# SensorSquare.net
KiCad netlist of a schematic drawn in Altium Designer
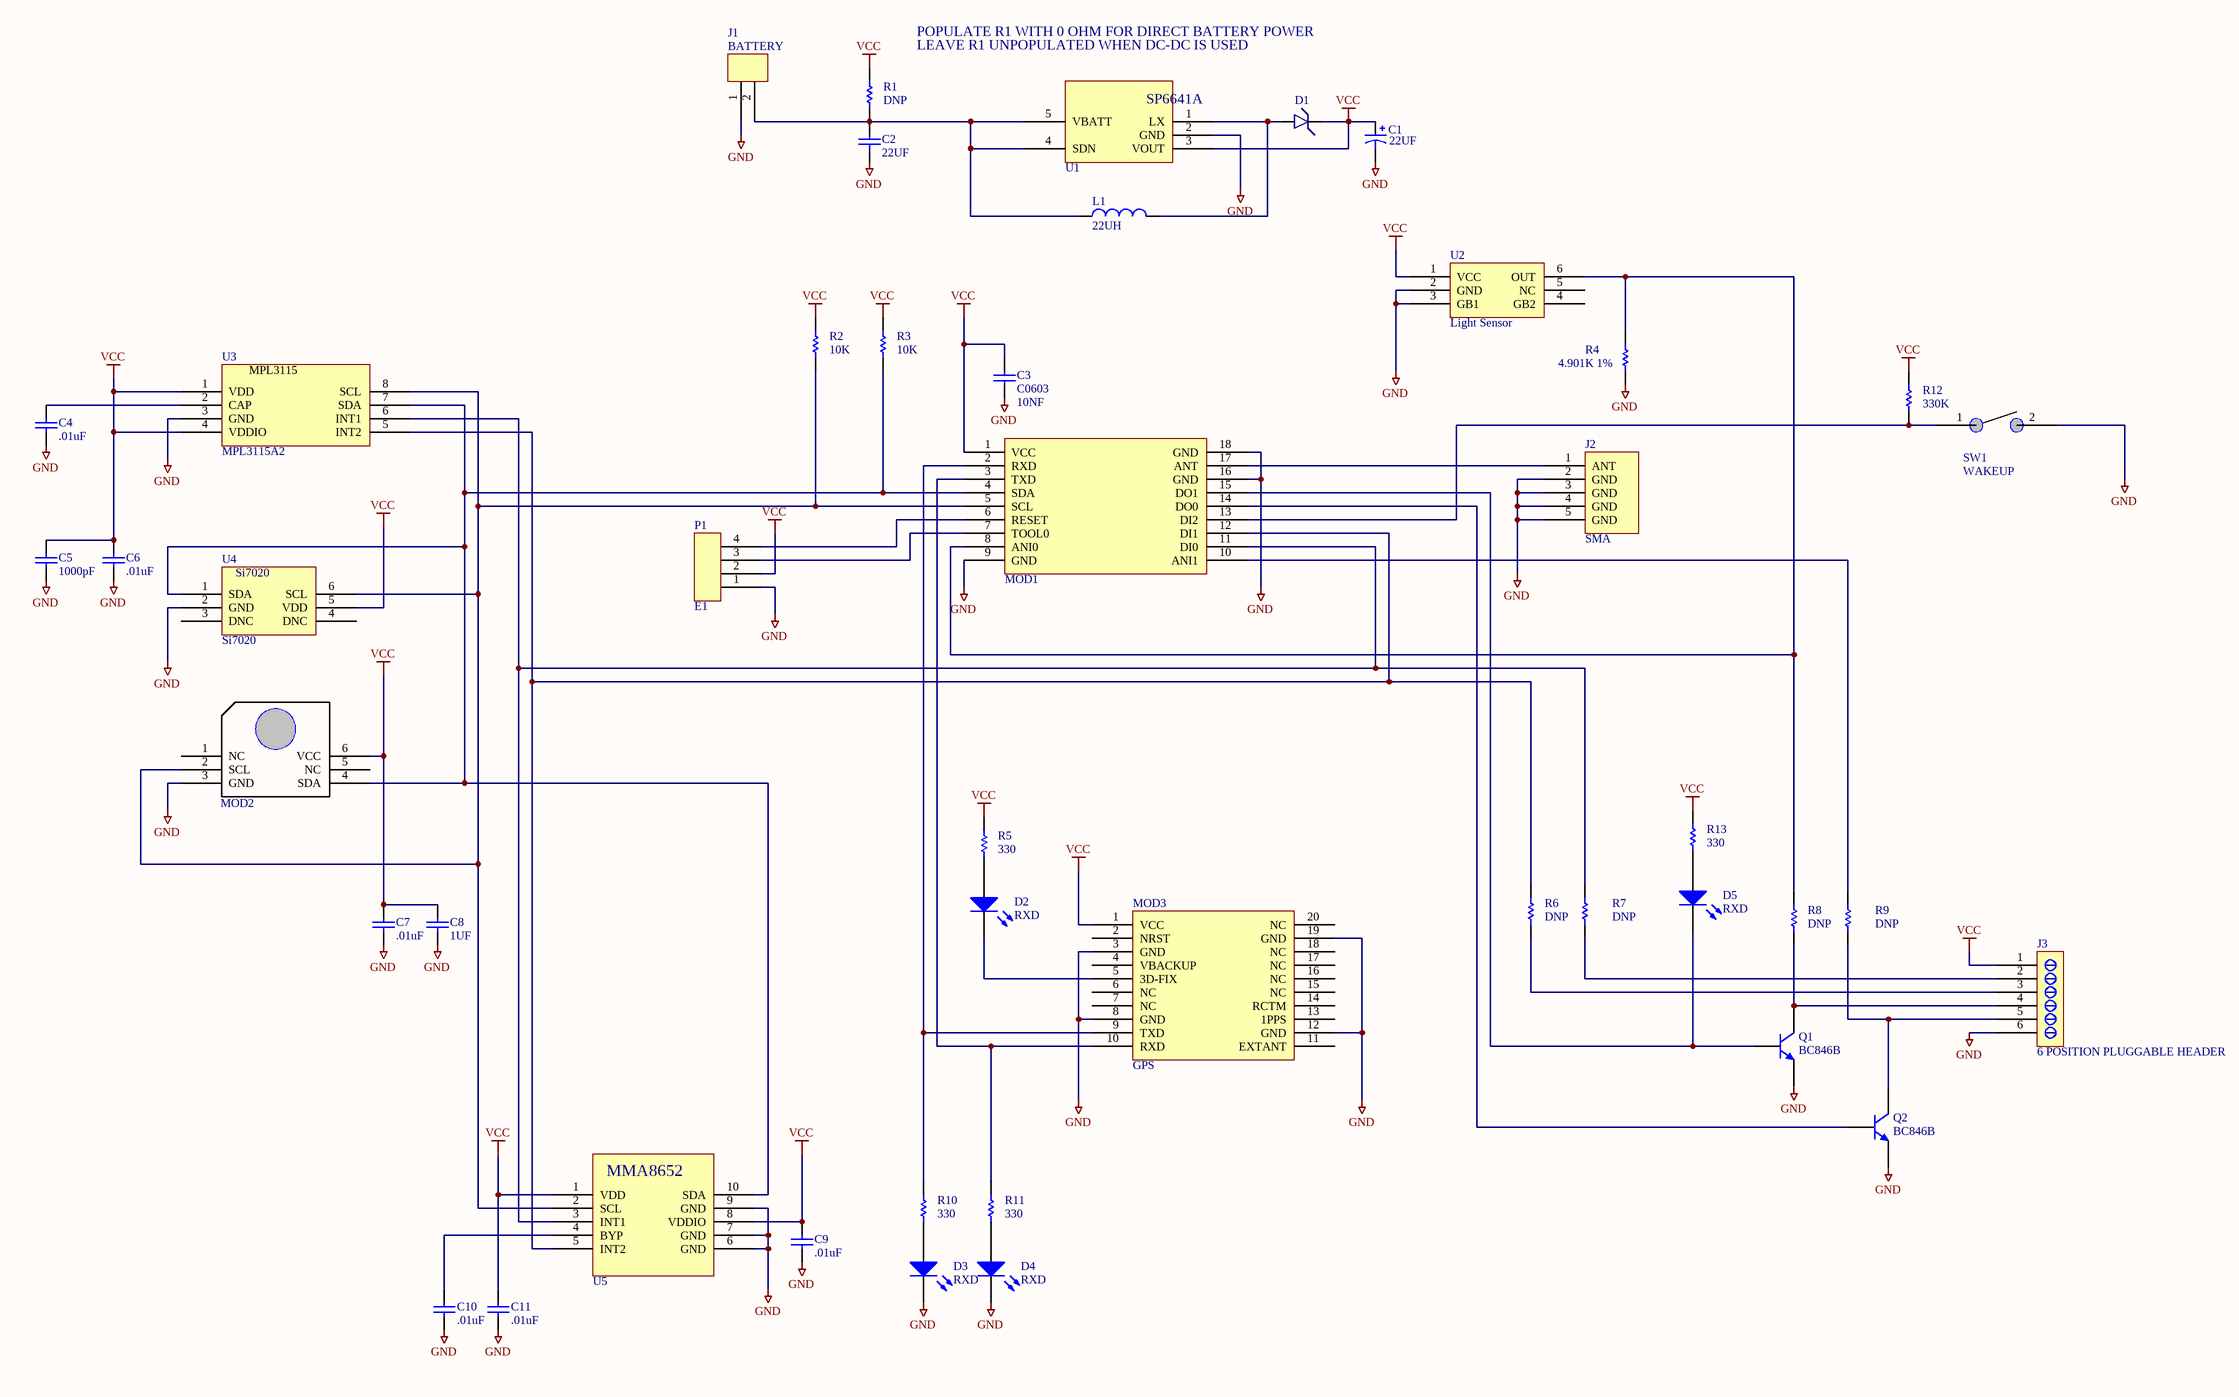
[diagram p0: SensorSquare.SchDoc]

(export (version "E")
  (design (tool "Eeschema 10.0.6"))
  (components
    (comp (ref "C1")
      (value "22UF")
      (footprint "1812")
      (description "Polarized Capacitor (Surface Mount)")
      (fields (field (name "VENDOR PART NUMBER") "647-F930J336MBA") (field (name "MANUFACTURER") "AVX"))
      (libsource (lib "Miscellaneous Devices") (part "Cap Pol3"))
    )
    (comp (ref "C2")
      (value "22UF")
      (footprint "1210")
      (description "Ceramic Chip Capacitor - Standard")
      (fields
        (field (name "MANUFACTURER") "AVX")
        (field (name "MANUFACTURER PART NUMBER") "TPSB107K006R0400")
      )
      (libsource (lib "KEMET Chip Capacitor") (part "C1210"))
    )
    (comp (ref "C3")
      (value "C0603")
      (footprint "0603")
      (description "Ceramic Chip Capacitor - Standard")
      (fields
        (field (name "ALTIUM_VALUE") "10NF")
        (field (name "VENDOR PART NUMBER") "140-CC504B103K-RC")
        (field (name "MANUFACTURER") "XICON")
      )
      (libsource (lib "KEMET Chip Capacitor") (part "C0603"))
    )
    (comp (ref "C4")
      (value ".01uF")
      (footprint "D6_0603_RES")
      (description "Ceramic Chip Capacitor - Standard")
      (fields
        (field (name "MANUFACTURER") "VISHAY")
        (field (name "MANUFACTURER PART NUMBER") "VJ0603A150JXACW1BC")
      )
      (libsource (lib "KEMET Chip Capacitor") (part "C1210"))
    )
    (comp (ref "C5")
      (value "1000pF")
      (footprint "D6_0603_RES")
      (description "Ceramic Chip Capacitor - Standard")
      (fields
        (field (name "MANUFACTURER") "VISHAY")
        (field (name "MANUFACTURER PART NUMBER") "VJ0603A150JXACW1BC")
      )
      (libsource (lib "KEMET Chip Capacitor") (part "C1210"))
    )
    (comp (ref "C6")
      (value ".01uF")
      (footprint "D6_0603_RES")
      (description "Ceramic Chip Capacitor - Standard")
      (fields
        (field (name "MANUFACTURER") "VISHAY")
        (field (name "MANUFACTURER PART NUMBER") "VJ0603A150JXACW1BC")
      )
      (libsource (lib "KEMET Chip Capacitor") (part "C1210"))
    )
    (comp (ref "C7")
      (value ".01uF")
      (footprint "D6_0603_RES")
      (description "Ceramic Chip Capacitor - Standard")
      (fields
        (field (name "MANUFACTURER") "VISHAY")
        (field (name "MANUFACTURER PART NUMBER") "VJ0603A150JXACW1BC")
      )
      (libsource (lib "KEMET Chip Capacitor") (part "C1210"))
    )
    (comp (ref "C8")
      (value "1UF")
      (footprint "D6_0603_RES")
      (description "Ceramic Chip Capacitor - Standard")
      (fields
        (field (name "MANUFACTURER") "VISHAY")
        (field (name "MANUFACTURER PART NUMBER") "VJ0603A150JXACW1BC")
      )
      (libsource (lib "KEMET Chip Capacitor") (part "C1210"))
    )
    (comp (ref "C9")
      (value ".01uF")
      (footprint "D6_0603_RES")
      (description "Ceramic Chip Capacitor - Standard")
      (fields
        (field (name "MANUFACTURER") "VISHAY")
        (field (name "MANUFACTURER PART NUMBER") "VJ0603A150JXACW1BC")
      )
      (libsource (lib "KEMET Chip Capacitor") (part "C1210"))
    )
    (comp (ref "C10")
      (value ".01uF")
      (footprint "D6_0603_RES")
      (description "Ceramic Chip Capacitor - Standard")
      (fields
        (field (name "MANUFACTURER") "VISHAY")
        (field (name "MANUFACTURER PART NUMBER") "VJ0603A150JXACW1BC")
      )
      (libsource (lib "KEMET Chip Capacitor") (part "C1210"))
    )
    (comp (ref "C11")
      (value ".01uF")
      (footprint "D6_0603_RES")
      (description "Ceramic Chip Capacitor - Standard")
      (fields
        (field (name "MANUFACTURER") "VISHAY")
        (field (name "MANUFACTURER PART NUMBER") "VJ0603A150JXACW1BC")
      )
      (libsource (lib "KEMET Chip Capacitor") (part "C1210"))
    )
    (comp (ref "D1")
      (value "SCHOTKY DIODE")
      (footprint "SOD123")
      (description "SCHOTKY DIODE SOD-123")
      (fields (field (name "MANUFACTURER") "ST") (field (name "MANUFACTURER PART NUMBER") "STPS0520Z"))
      (libsource (lib "D6 Labs") (part "SCHOTKY DIODE"))
    )
    (comp (ref "D2")
      (value "RXD")
      (footprint "3.2X1.6X1.1")
      (description "Typical RED, GREEN, YELLOW, AMBER GaAs LED")
      (fields (field (name "PUBLISHER") "Altium Limited"))
      (libsource (lib "Miscellaneous Devices") (part "LED2"))
    )
    (comp (ref "D3")
      (value "RXD")
      (footprint "3.2X1.6X1.1")
      (description "Typical RED, GREEN, YELLOW, AMBER GaAs LED")
      (fields (field (name "PUBLISHER") "Altium Limited"))
      (libsource (lib "Miscellaneous Devices") (part "LED2"))
    )
    (comp (ref "D4")
      (value "RXD")
      (footprint "3.2X1.6X1.1")
      (description "Typical RED, GREEN, YELLOW, AMBER GaAs LED")
      (fields (field (name "PUBLISHER") "Altium Limited"))
      (libsource (lib "Miscellaneous Devices") (part "LED2"))
    )
    (comp (ref "D5")
      (value "RXD")
      (footprint "3.2X1.6X1.1")
      (description "Typical RED, GREEN, YELLOW, AMBER GaAs LED")
      (fields (field (name "PUBLISHER") "Altium Limited"))
      (libsource (lib "Miscellaneous Devices") (part "LED2"))
    )
    (comp (ref "J1")
      (value "BATTERY")
      (footprint "S2B-PH-SM4")
      (description "2 POSITION, 2MM RIGHT ANGLE CONNECTOR")
      (fields (field (name "MANUFACTURER") "JST") (field (name "MANUFACTURER PART NUMBER") "S2B-PH-SM4-TB"))
      (libsource (lib "D6 Connectors") (part "S2B-PH-SM4-TB"))
    )
    (comp (ref "J2")
      (value "SMA")
      (footprint "RPSMA-EDGEMOUNT")
      (libsource (lib "D6 Connectors") (part "SMA"))
    )
    (comp (ref "J3")
      (value "6 POSITION PLUGGABLE HEADER")
      (footprint "6POS 5.08MM PLUGGABLE")
      (fields
        (field (name "MANUFACTURER") "FCI CONN")
        (field (name "MANUFACTURER PART NUMBER") "20020110-H061A01LF")
        (field (name "VENDOR PART NUMBER") "649-20020110-H061A01LF")
      )
      (libsource (lib "D6 Connectors") (part "6 POSITION PLUGGABLE HEADER"))
    )
    (comp (ref "L1")
      (value "22UH")
      (footprint "INDC4532")
      (description "Inductor")
      (fields
        (field (name "MANUFACTURER") "TDK")
        (field (name "MANUFACTURER PART NUMBER") "NLC453232T-220K-PF")
      )
      (libsource (lib "Miscellaneous Devices") (part "Inductor"))
    )
    (comp (ref "MOD1")
      (value "WhiskerModule")
      (footprint "WHISKER_SMD_DOLLY")
      (description "Whisker Footprint")
      (libsource (lib "D6 Labs") (part "WhiskerModule"))
    )
    (comp (ref "MOD2")
      (value "IAQ_ENGINE")
      (footprint "IAQENGINE")
      (description "Indoor Air Quality Sensor Module")
      (libsource (lib "AppliedSensor") (part "IAQ_ENGINE"))
    )
    (comp (ref "MOD3")
      (value "GPS")
      (footprint "GPS-SOP20")
      (fields
        (field (name "MANUFACTURER") "GTOP")
        (field (name "MANUFACTURER PART NUMBER") "FGPMMOPA6H")
        (field (name "VENDOR PART NUMBER") "PID790")
      )
      (libsource (lib "adafruit") (part "ULTIMATEGPS"))
    )
    (comp (ref "P1")
      (value "E1")
      (footprint "2MM4PINHDR")
      (libsource (lib "D6 Connectors") (part "2MM4PINHDR"))
    )
    (comp (ref "Q1")
      (value "BC846B")
      (footprint "SOT23")
      (description "SOT23 NPN Silicon Planar General Purpose Transistor")
      (fields
        (field (name "MANUFACTURER") "ON SEMI")
        (field (name "MANUFACTURER PART NUMBER") "MMUN2232LT1G")
        (field (name "PUBLISHER") "Altium Limited")
      )
      (libsource (lib "Zetex Discrete BJT") (part "BC846B"))
    )
    (comp (ref "Q2")
      (value "BC846B")
      (footprint "SOT23")
      (description "SOT23 NPN Silicon Planar General Purpose Transistor")
      (fields
        (field (name "MANUFACTURER") "ON SEMI")
        (field (name "MANUFACTURER PART NUMBER") "MMUN2232LT1G")
        (field (name "PUBLISHER") "Altium Limited")
      )
      (libsource (lib "Zetex Discrete BJT") (part "BC846B"))
    )
    (comp (ref "R1")
      (value "DNP")
      (footprint "ERA-0603")
      (fields (field (name "VENDOR PART NUMBER") "301-330-RC") (field (name "MANUFACTURER") "XICON"))
      (libsource (lib "Panasonic Resistor") (part "ERA3Y"))
    )
    (comp (ref "R2")
      (value "10K")
      (footprint "3-0603")
      (fields (field (name "PUBLISHER") "Altium Limited"))
      (libsource (lib "Panasonic Resistor") (part "ERJ3BQ"))
    )
    (comp (ref "R3")
      (value "10K")
      (footprint "3-0603")
      (fields (field (name "PUBLISHER") "Altium Limited"))
      (libsource (lib "Panasonic Resistor") (part "ERJ3BQ"))
    )
    (comp (ref "R4")
      (value "4.901K 1%")
      (footprint "D6_0603_RES")
      (fields (field (name "VENDOR PART NUMBER") "301-100K-RC") (field (name "MANUFACTURER") "XICON"))
      (libsource (lib "Panasonic Resistor") (part "ERA3Y"))
    )
    (comp (ref "R5")
      (value "330")
      (footprint "ERA-0603")
      (fields (field (name "VENDOR PART NUMBER") "301-330-RC") (field (name "MANUFACTURER") "XICON"))
      (libsource (lib "Panasonic Resistor") (part "ERA3Y"))
    )
    (comp (ref "R6")
      (value "DNP")
      (footprint "ERA-0603")
      (fields (field (name "VENDOR PART NUMBER") "301-330-RC") (field (name "MANUFACTURER") "XICON"))
      (libsource (lib "Panasonic Resistor") (part "ERA3Y"))
    )
    (comp (ref "R7")
      (value "DNP")
      (footprint "ERA-0603")
      (fields (field (name "VENDOR PART NUMBER") "301-330-RC") (field (name "MANUFACTURER") "XICON"))
      (libsource (lib "Panasonic Resistor") (part "ERA3Y"))
    )
    (comp (ref "R8")
      (value "DNP")
      (footprint "ERA-0603")
      (fields (field (name "VENDOR PART NUMBER") "301-330-RC") (field (name "MANUFACTURER") "XICON"))
      (libsource (lib "Panasonic Resistor") (part "ERA3Y"))
    )
    (comp (ref "R9")
      (value "DNP")
      (footprint "ERA-0603")
      (fields (field (name "VENDOR PART NUMBER") "301-330-RC") (field (name "MANUFACTURER") "XICON"))
      (libsource (lib "Panasonic Resistor") (part "ERA3Y"))
    )
    (comp (ref "R10")
      (value "330")
      (footprint "ERA-0603")
      (fields (field (name "VENDOR PART NUMBER") "301-330-RC") (field (name "MANUFACTURER") "XICON"))
      (libsource (lib "Panasonic Resistor") (part "ERA3Y"))
    )
    (comp (ref "R11")
      (value "330")
      (footprint "ERA-0603")
      (fields (field (name "VENDOR PART NUMBER") "301-330-RC") (field (name "MANUFACTURER") "XICON"))
      (libsource (lib "Panasonic Resistor") (part "ERA3Y"))
    )
    (comp (ref "R12")
      (value "330K")
      (footprint "D6_0603_RES")
      (fields (field (name "VENDOR PART NUMBER") "301-100K-RC") (field (name "MANUFACTURER") "XICON"))
      (libsource (lib "Panasonic Resistor") (part "ERA3Y"))
    )
    (comp (ref "R13")
      (value "330")
      (footprint "ERA-0603")
      (fields (field (name "VENDOR PART NUMBER") "301-330-RC") (field (name "MANUFACTURER") "XICON"))
      (libsource (lib "Panasonic Resistor") (part "ERA3Y"))
    )
    (comp (ref "SW1")
      (value "WAKEUP")
      (footprint "MK23-35-B-2")
      (description "SMT Reed Switch")
      (fields (field (name "MANUFACTURER") "MEDER") (field (name "MANUFACTURER PART NUMBER") "MK23-35-B-2"))
      (libsource (lib "Meder") (part "MK23-35-B-2"))
    )
    (comp (ref "U1")
      (value "500MA ALKALINE D~{C}DC BOOST REGULATOR SOT-23")
      (footprint "SOT95P280X110-5N")
      (description "SP6641A")
      (fields
        (field (name "MANUFACTURER") "SIPEX")
        (field (name "MANUFACTURER PART NUMBER") "SP6641BEK-L-3-3")
      )
      (libsource (lib "exar") (part "500MA ALKALINE DC{backslash}DC BOOST REGULATOR SOT-23"))
    )
    (comp (ref "U2")
      (value "Light Sensor")
      (footprint "CUDFN6")
      (description "Ambient Light Sensor with Dark Comp")
      (fields
        (field (name "MANUFACTURER") "ON SEMI")
        (field (name "MANUFACTURER PART NUMBER") "NOA1212CUTAG")
      )
      (libsource (lib "On Semi") (part "NOA1212"))
    )
    (comp (ref "U3")
      (value "MPL3115A2")
      (footprint "LGA8")
      (description "Precision altimeter")
      (fields (field (name "MANUFACTURER") "FREESCALE") (field (name "VENDOR PART NUMBER") "841-MPL3115A2R1"))
      (libsource (lib "FreeScaleSensors") (part "MPL3115A2"))
    )
    (comp (ref "U4")
      (value "Si7020")
      (footprint "DFN6")
      (description "I2C Temperature and Humidity Sensor")
      (fields
        (field (name "VENDOR PART NUMBER") "634- Si7020-A10-GM")
        (field (name "MANUFACTURER") "SILICON LABORATORIES")
      )
      (libsource (lib "SiLabs") (part "Si7020"))
    )
    (comp (ref "U5")
      (value "MMA8652")
      (footprint "DFN10")
      (description "3-axis, 12-bit accelerometer")
      (fields
        (field (name "MANUFACTURER") "FREESCALE")
        (field (name "MANUFACTURER PART NUMBER") "863-NOA1212CUTAG")
      )
      (libsource (lib "FreeScaleSensors") (part "MMA8652"))
    )
  )
  (nets
    (net (code "1") (name "GND") (class "Default")
      (node (ref "C1") (pin "2") (pinfunction "2_2") (pintype "passive"))
      (node (ref "C10") (pin "1") (pinfunction "1_1") (pintype "passive"))
      (node (ref "C11") (pin "1") (pinfunction "1_1") (pintype "passive"))
      (node (ref "C2") (pin "1") (pinfunction "1_1") (pintype "passive"))
      (node (ref "C3") (pin "1") (pinfunction "1_1") (pintype "passive"))
      (node (ref "C4") (pin "1") (pinfunction "1_1") (pintype "passive"))
      (node (ref "C5") (pin "1") (pinfunction "1_1") (pintype "passive"))
      (node (ref "C6") (pin "1") (pinfunction "1_1") (pintype "passive"))
      (node (ref "C7") (pin "1") (pinfunction "1_1") (pintype "passive"))
      (node (ref "C8") (pin "1") (pinfunction "1_1") (pintype "passive"))
      (node (ref "C9") (pin "1") (pinfunction "1_1") (pintype "passive"))
      (node (ref "D3") (pin "2") (pinfunction "K_2") (pintype "passive"))
      (node (ref "D4") (pin "2") (pinfunction "K_2") (pintype "passive"))
      (node (ref "J1") (pin "1") (pintype "passive"))
      (node (ref "J2") (pin "2") (pinfunction "GND_2") (pintype "passive"))
      (node (ref "J2") (pin "3") (pinfunction "GND_3") (pintype "passive"))
      (node (ref "J2") (pin "4") (pinfunction "GND_4") (pintype "passive"))
      (node (ref "J2") (pin "5") (pinfunction "GND_5") (pintype "passive"))
      (node (ref "J3") (pin "6") (pinfunction "RESERVED_6") (pintype "passive"))
      (node (ref "MOD1") (pin "16") (pinfunction "GND_16") (pintype "passive"))
      (node (ref "MOD1") (pin "18") (pinfunction "GND_18") (pintype "passive"))
      (node (ref "MOD1") (pin "9") (pinfunction "GND_9") (pintype "passive"))
      (node (ref "MOD2") (pin "3") (pinfunction "GND_3") (pintype "passive"))
      (node (ref "MOD3") (pin "12") (pinfunction "GND_12") (pintype "passive"))
      (node (ref "MOD3") (pin "19") (pinfunction "GND_19") (pintype "passive"))
      (node (ref "MOD3") (pin "3") (pinfunction "GND_3") (pintype "passive"))
      (node (ref "MOD3") (pin "8") (pinfunction "GND_8") (pintype "passive"))
      (node (ref "P1") (pin "1") (pinfunction "RESET_1") (pintype "power_in"))
      (node (ref "Q1") (pin "2") (pinfunction "E_2") (pintype "passive"))
      (node (ref "Q2") (pin "2") (pinfunction "E_2") (pintype "passive"))
      (node (ref "R4") (pin "2") (pinfunction "2_2") (pintype "passive"))
      (node (ref "SW1") (pin "2") (pinfunction "2_2") (pintype "passive"))
      (node (ref "U1") (pin "2") (pinfunction "GND_2") (pintype "passive"))
      (node (ref "U2") (pin "2") (pinfunction "GND_2") (pintype "power_in"))
      (node (ref "U2") (pin "3") (pinfunction "GB1_3") (pintype "power_in"))
      (node (ref "U3") (pin "3") (pinfunction "GND_3") (pintype "power_in"))
      (node (ref "U4") (pin "2") (pinfunction "GND_2") (pintype "passive"))
      (node (ref "U5") (pin "6") (pinfunction "GND_6") (pintype "passive"))
      (node (ref "U5") (pin "7") (pinfunction "GND_7") (pintype "passive"))
      (node (ref "U5") (pin "9") (pinfunction "GND_9") (pintype "passive"))
    )
    (net (code "2") (name "Net-(D2-A)") (class "Default")
      (node (ref "D2") (pin "1") (pinfunction "A_1") (pintype "passive"))
      (node (ref "R5") (pin "2") (pinfunction "2_2") (pintype "passive"))
    )
    (net (code "3") (name "Net-(D2-K)") (class "Default")
      (node (ref "D2") (pin "2") (pinfunction "K_2") (pintype "passive"))
      (node (ref "MOD3") (pin "5") (pinfunction "3D-FIX_5") (pintype "passive"))
    )
    (net (code "4") (name "Net-(D3-A)") (class "Default")
      (node (ref "D3") (pin "1") (pinfunction "A_1") (pintype "passive"))
      (node (ref "R10") (pin "2") (pinfunction "2_2") (pintype "passive"))
    )
    (net (code "5") (name "Net-(D4-A)") (class "Default")
      (node (ref "D4") (pin "1") (pinfunction "A_1") (pintype "passive"))
      (node (ref "R11") (pin "2") (pinfunction "2_2") (pintype "passive"))
    )
    (net (code "6") (name "Net-(D5-A)") (class "Default")
      (node (ref "D5") (pin "1") (pinfunction "A_1") (pintype "passive"))
      (node (ref "R13") (pin "2") (pinfunction "2_2") (pintype "passive"))
    )
    (net (code "7") (name "Net-(D5-K)") (class "Default")
      (node (ref "D5") (pin "2") (pinfunction "K_2") (pintype "passive"))
      (node (ref "MOD1") (pin "15") (pinfunction "DO1_15") (pintype "passive"))
      (node (ref "Q1") (pin "3") (pinfunction "B_3") (pintype "passive"))
    )
    (net (code "8") (name "Net-(J2-ANT)") (class "Default")
      (node (ref "J2") (pin "1") (pinfunction "ANT_1") (pintype "passive"))
      (node (ref "MOD1") (pin "17") (pinfunction "ANT_17") (pintype "passive"))
    )
    (net (code "9") (name "Net-(J3-RESERVED-Pad2)") (class "Default")
      (node (ref "J3") (pin "2") (pinfunction "RESERVED_2") (pintype "passive"))
      (node (ref "R7") (pin "2") (pinfunction "2_2") (pintype "passive"))
    )
    (net (code "10") (name "Net-(J3-RESERVED-Pad3)") (class "Default")
      (node (ref "J3") (pin "3") (pinfunction "RESERVED_3") (pintype "passive"))
      (node (ref "R6") (pin "2") (pinfunction "2_2") (pintype "passive"))
    )
    (net (code "11") (name "Net-(MOD1-ANI0)") (class "Default")
      (node (ref "MOD1") (pin "8") (pinfunction "ANI0_8") (pintype "passive"))
      (node (ref "R4") (pin "1") (pinfunction "1_1") (pintype "passive"))
      (node (ref "R8") (pin "1") (pinfunction "1_1") (pintype "passive"))
      (node (ref "U2") (pin "6") (pinfunction "OUT_6") (pintype "power_in"))
    )
    (net (code "12") (name "Net-(MOD1-ANI1)") (class "Default")
      (node (ref "MOD1") (pin "10") (pinfunction "ANI1_10") (pintype "passive"))
      (node (ref "R9") (pin "1") (pinfunction "1_1") (pintype "passive"))
    )
    (net (code "13") (name "Net-(MOD1-DI0)") (class "Default")
      (node (ref "MOD1") (pin "11") (pinfunction "DI0_11") (pintype "passive"))
      (node (ref "R7") (pin "1") (pinfunction "1_1") (pintype "passive"))
      (node (ref "U3") (pin "6") (pinfunction "INT1_6") (pintype "power_in"))
      (node (ref "U5") (pin "3") (pinfunction "INT1_3") (pintype "passive"))
    )
    (net (code "14") (name "Net-(MOD1-DI1)") (class "Default")
      (node (ref "MOD1") (pin "12") (pinfunction "DI1_12") (pintype "passive"))
      (node (ref "R6") (pin "1") (pinfunction "1_1") (pintype "passive"))
      (node (ref "U3") (pin "5") (pinfunction "INT2_5") (pintype "power_in"))
      (node (ref "U5") (pin "5") (pinfunction "INT2_5") (pintype "passive"))
    )
    (net (code "15") (name "Net-(MOD1-DI2)") (class "Default")
      (node (ref "MOD1") (pin "13") (pinfunction "DI2_13") (pintype "passive"))
      (node (ref "R12") (pin "2") (pinfunction "2_2") (pintype "passive"))
      (node (ref "SW1") (pin "1") (pinfunction "1_1") (pintype "passive"))
    )
    (net (code "16") (name "Net-(MOD1-DO0)") (class "Default")
      (node (ref "MOD1") (pin "14") (pinfunction "DO0_14") (pintype "passive"))
      (node (ref "Q2") (pin "3") (pinfunction "B_3") (pintype "passive"))
    )
    (net (code "17") (name "Net-(MOD1-RESET)") (class "Default")
      (node (ref "MOD1") (pin "6") (pinfunction "RESET_6") (pintype "passive"))
      (node (ref "P1") (pin "4") (pinfunction "RESET_4") (pintype "power_in"))
    )
    (net (code "18") (name "Net-(MOD1-RXD)") (class "Default")
      (node (ref "MOD1") (pin "2") (pinfunction "RXD_2") (pintype "passive"))
      (node (ref "MOD3") (pin "9") (pinfunction "TXD_9") (pintype "passive"))
      (node (ref "R10") (pin "1") (pinfunction "1_1") (pintype "passive"))
    )
    (net (code "19") (name "Net-(MOD1-SCL)") (class "Default")
      (node (ref "MOD1") (pin "5") (pinfunction "SCL_5") (pintype "passive"))
      (node (ref "MOD2") (pin "2") (pinfunction "SCL_2") (pintype "passive"))
      (node (ref "R2") (pin "1") (pinfunction "1_1") (pintype "passive"))
      (node (ref "U3") (pin "8") (pinfunction "SCL_8") (pintype "power_in"))
      (node (ref "U4") (pin "6") (pinfunction "SCL_6") (pintype "passive"))
      (node (ref "U5") (pin "2") (pinfunction "SCL_2") (pintype "passive"))
    )
    (net (code "20") (name "Net-(MOD1-SDA)") (class "Default")
      (node (ref "MOD1") (pin "4") (pinfunction "SDA_4") (pintype "passive"))
      (node (ref "MOD2") (pin "4") (pinfunction "SDA_4") (pintype "passive"))
      (node (ref "R3") (pin "1") (pinfunction "1_1") (pintype "passive"))
      (node (ref "U3") (pin "7") (pinfunction "SDA_7") (pintype "power_in"))
      (node (ref "U4") (pin "1") (pinfunction "SDA_1") (pintype "passive"))
      (node (ref "U5") (pin "10") (pinfunction "SDA_10") (pintype "passive"))
    )
    (net (code "21") (name "Net-(MOD1-TOOL0)") (class "Default")
      (node (ref "MOD1") (pin "7") (pinfunction "TOOL0_7") (pintype "passive"))
      (node (ref "P1") (pin "3") (pinfunction "RESET_3") (pintype "power_in"))
    )
    (net (code "22") (name "Net-(MOD1-TXD)") (class "Default")
      (node (ref "MOD1") (pin "3") (pinfunction "TXD_3") (pintype "passive"))
      (node (ref "MOD3") (pin "10") (pinfunction "RXD_10") (pintype "passive"))
      (node (ref "R11") (pin "1") (pinfunction "1_1") (pintype "passive"))
    )
    (net (code "23") (name "Net-(Q1-C)") (class "Default")
      (node (ref "J3") (pin "4") (pinfunction "RESERVED_4") (pintype "passive"))
      (node (ref "Q1") (pin "1") (pinfunction "C_1") (pintype "passive"))
      (node (ref "R8") (pin "2") (pinfunction "2_2") (pintype "passive"))
    )
    (net (code "24") (name "Net-(Q2-C)") (class "Default")
      (node (ref "J3") (pin "5") (pinfunction "RESERVED_5") (pintype "passive"))
      (node (ref "Q2") (pin "1") (pinfunction "C_1") (pintype "passive"))
      (node (ref "R9") (pin "2") (pinfunction "2_2") (pintype "passive"))
    )
    (net (code "25") (name "Net-(U1-LX)") (class "Default")
      (node (ref "D1") (pin "A") (pinfunction "VBATT_A") (pintype "passive"))
      (node (ref "L1") (pin "2") (pinfunction "2_2") (pintype "passive"))
      (node (ref "U1") (pin "1") (pinfunction "LX_1") (pintype "passive"))
    )
    (net (code "26") (name "Net-(U1-SDN)") (class "Default")
      (node (ref "C2") (pin "2") (pinfunction "2_2") (pintype "passive"))
      (node (ref "J1") (pin "2") (pintype "passive"))
      (node (ref "L1") (pin "1") (pinfunction "1_1") (pintype "passive"))
      (node (ref "R1") (pin "2") (pinfunction "2_2") (pintype "passive"))
      (node (ref "U1") (pin "4") (pinfunction "SDN_4") (pintype "passive"))
      (node (ref "U1") (pin "5") (pinfunction "VBATT_5") (pintype "passive"))
    )
    (net (code "27") (name "Net-(U3-CAP)") (class "Default")
      (node (ref "C4") (pin "2") (pinfunction "2_2") (pintype "passive"))
      (node (ref "U3") (pin "2") (pinfunction "CAP_2") (pintype "power_in"))
    )
    (net (code "28") (name "Net-(U5-BYP)") (class "Default")
      (node (ref "C10") (pin "2") (pinfunction "2_2") (pintype "passive"))
      (node (ref "U5") (pin "4") (pinfunction "BYP_4") (pintype "passive"))
    )
    (net (code "29") (name "VCC") (class "Default")
      (node (ref "C1") (pin "1") (pinfunction "1_1") (pintype "passive"))
      (node (ref "C11") (pin "2") (pinfunction "2_2") (pintype "passive"))
      (node (ref "C3") (pin "2") (pinfunction "2_2") (pintype "passive"))
      (node (ref "C5") (pin "2") (pinfunction "2_2") (pintype "passive"))
      (node (ref "C6") (pin "2") (pinfunction "2_2") (pintype "passive"))
      (node (ref "C7") (pin "2") (pinfunction "2_2") (pintype "passive"))
      (node (ref "C8") (pin "2") (pinfunction "2_2") (pintype "passive"))
      (node (ref "C9") (pin "2") (pinfunction "2_2") (pintype "passive"))
      (node (ref "D1") (pin "K") (pinfunction "VBATT_K") (pintype "passive"))
      (node (ref "J3") (pin "1") (pinfunction "RESERVED_1") (pintype "passive"))
      (node (ref "MOD1") (pin "1") (pinfunction "VCC_1") (pintype "passive"))
      (node (ref "MOD2") (pin "6") (pinfunction "VCC_6") (pintype "passive"))
      (node (ref "MOD3") (pin "1") (pinfunction "VCC_1") (pintype "passive"))
      (node (ref "P1") (pin "2") (pinfunction "RESET_2") (pintype "power_in"))
      (node (ref "R1") (pin "1") (pinfunction "1_1") (pintype "passive"))
      (node (ref "R12") (pin "1") (pinfunction "1_1") (pintype "passive"))
      (node (ref "R13") (pin "1") (pinfunction "1_1") (pintype "passive"))
      (node (ref "R2") (pin "2") (pinfunction "2_2") (pintype "passive"))
      (node (ref "R3") (pin "2") (pinfunction "2_2") (pintype "passive"))
      (node (ref "R5") (pin "1") (pinfunction "1_1") (pintype "passive"))
      (node (ref "U1") (pin "3") (pinfunction "VOUT_3") (pintype "passive"))
      (node (ref "U2") (pin "1") (pinfunction "VCC_1") (pintype "power_in"))
      (node (ref "U3") (pin "1") (pinfunction "VDD_1") (pintype "power_in"))
      (node (ref "U3") (pin "4") (pinfunction "VDDIO_4") (pintype "power_in"))
      (node (ref "U4") (pin "5") (pinfunction "VDD_5") (pintype "passive"))
      (node (ref "U5") (pin "1") (pinfunction "VDD_1") (pintype "passive"))
      (node (ref "U5") (pin "8") (pinfunction "VDDIO_8") (pintype "passive"))
    )
    (net (code "30") (name "unconnected-(MOD2-NC-Pad1)") (class "Default")
      (node (ref "MOD2") (pin "1") (pinfunction "NC_1") (pintype "passive"))
    )
    (net (code "31") (name "unconnected-(MOD2-NC-Pad5)") (class "Default")
      (node (ref "MOD2") (pin "5") (pinfunction "NC_5") (pintype "passive"))
    )
    (net (code "32") (name "unconnected-(MOD3-1PPS-Pad13)") (class "Default")
      (node (ref "MOD3") (pin "13") (pinfunction "1PPS_13") (pintype "passive"))
    )
    (net (code "33") (name "unconnected-(MOD3-EXTANT-Pad11)") (class "Default")
      (node (ref "MOD3") (pin "11") (pinfunction "EXTANT_11") (pintype "passive"))
    )
    (net (code "34") (name "unconnected-(MOD3-NC-Pad6)") (class "Default")
      (node (ref "MOD3") (pin "6") (pinfunction "NC_6") (pintype "passive"))
    )
    (net (code "35") (name "unconnected-(MOD3-NC-Pad7)") (class "Default")
      (node (ref "MOD3") (pin "7") (pinfunction "NC_7") (pintype "passive"))
    )
    (net (code "36") (name "unconnected-(MOD3-NC-Pad15)") (class "Default")
      (node (ref "MOD3") (pin "15") (pinfunction "NC_15") (pintype "passive"))
    )
    (net (code "37") (name "unconnected-(MOD3-NC-Pad16)") (class "Default")
      (node (ref "MOD3") (pin "16") (pinfunction "NC_16") (pintype "passive"))
    )
    (net (code "38") (name "unconnected-(MOD3-NC-Pad17)") (class "Default")
      (node (ref "MOD3") (pin "17") (pinfunction "NC_17") (pintype "passive"))
    )
    (net (code "39") (name "unconnected-(MOD3-NC-Pad18)") (class "Default")
      (node (ref "MOD3") (pin "18") (pinfunction "NC_18") (pintype "passive"))
    )
    (net (code "40") (name "unconnected-(MOD3-NC-Pad20)") (class "Default")
      (node (ref "MOD3") (pin "20") (pinfunction "NC_20") (pintype "passive"))
    )
    (net (code "41") (name "unconnected-(MOD3-NRST-Pad2)") (class "Default")
      (node (ref "MOD3") (pin "2") (pinfunction "NRST_2") (pintype "passive"))
    )
    (net (code "42") (name "unconnected-(MOD3-RCTM-Pad14)") (class "Default")
      (node (ref "MOD3") (pin "14") (pinfunction "RCTM_14") (pintype "passive"))
    )
    (net (code "43") (name "unconnected-(MOD3-VBACKUP-Pad4)") (class "Default")
      (node (ref "MOD3") (pin "4") (pinfunction "VBACKUP_4") (pintype "passive"))
    )
    (net (code "44") (name "unconnected-(U2-GB2-Pad4)") (class "Default")
      (node (ref "U2") (pin "4") (pinfunction "GB2_4") (pintype "power_in"))
    )
    (net (code "45") (name "unconnected-(U2-NC-Pad5)") (class "Default")
      (node (ref "U2") (pin "5") (pinfunction "NC_5") (pintype "power_in"))
    )
    (net (code "46") (name "unconnected-(U4-DNC-Pad3)") (class "Default")
      (node (ref "U4") (pin "3") (pinfunction "DNC_3") (pintype "passive"))
    )
    (net (code "47") (name "unconnected-(U4-DNC-Pad4)") (class "Default")
      (node (ref "U4") (pin "4") (pinfunction "DNC_4") (pintype "passive"))
    )
  )
)
